# projet_electronique.net
KiCad netlist of a schematic drawn in EAGLE
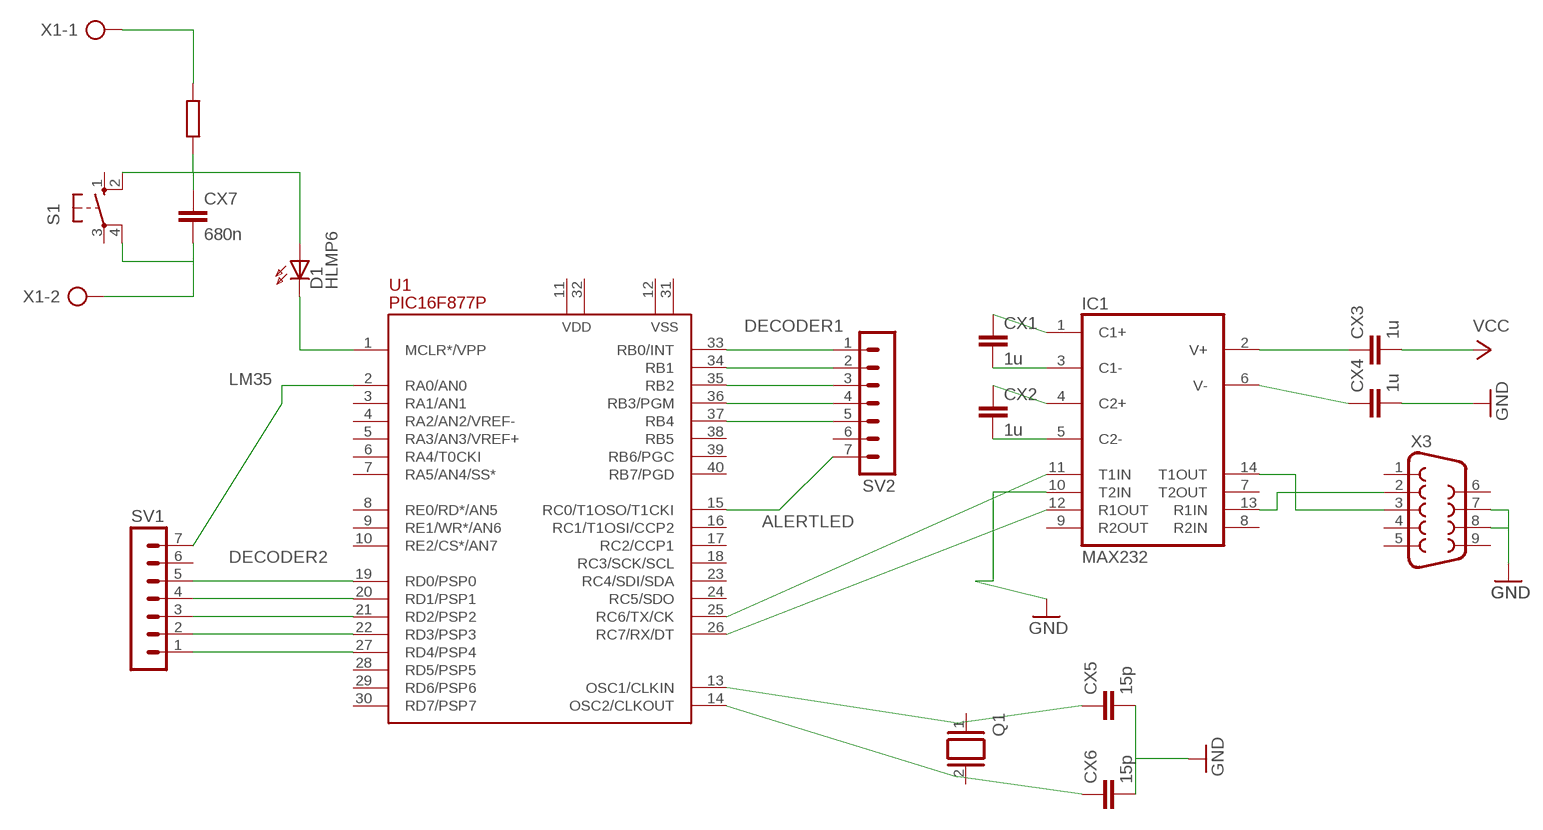
[diagram p0: schematic, sheet 1]

(export (version "E")
  (design (tool "Eeschema 10.0.6"))
  (components
    (comp (ref "CX1")
      (value "1u")
      (footprint "eagle-import:XC10B5")
      (libsource (lib "eagle-import") (part "CXXC10B5"))
    )
    (comp (ref "CX2")
      (value "1u")
      (footprint "eagle-import:XC10B5")
      (libsource (lib "eagle-import") (part "CXXC10B5"))
    )
    (comp (ref "CX3")
      (value "1u")
      (footprint "eagle-import:XC10B5")
      (libsource (lib "eagle-import") (part "CXXC10B5"))
    )
    (comp (ref "CX4")
      (value "1u")
      (footprint "eagle-import:XC10B5")
      (libsource (lib "eagle-import") (part "CXXC10B5"))
    )
    (comp (ref "CX5")
      (value "15p")
      (footprint "eagle-import:XC10B5")
      (libsource (lib "eagle-import") (part "CXXC10B5"))
    )
    (comp (ref "CX6")
      (value "15p")
      (footprint "eagle-import:XC10B5")
      (libsource (lib "eagle-import") (part "CXXC10B5"))
    )
    (comp (ref "CX7")
      (value "680n")
      (footprint "eagle-import:XC10B5")
      (libsource (lib "eagle-import") (part "CXXC10B5"))
    )
    (comp (ref "D1")
      (value "HLMP6")
      (footprint "eagle-import:HLMP6")
      (fields (field (name "MF") "AGILENT TECHNOLOGIES") (field (name "MPN") "HLMP-6500"))
      (libsource (lib "eagle-import") (part "HLMP6"))
    )
    (comp (ref "IC1")
      (value "MAX232")
      (footprint "eagle-import:DIL16")
      (fields (field (name "MF") "MAXIM") (field (name "MPN") "MAX232ACPE+"))
      (libsource (lib "eagle-import") (part "MAX232"))
    )
    (comp (ref "Q1")
      (value "XTAL")
      (footprint "eagle-import:Q")
      (libsource (lib "eagle-import") (part "XTAL"))
    )
    (comp (ref "S1")
      (value "10-XX")
      (footprint "eagle-import:B3F-10XX")
      (fields (field (name "MPN") "B3F-1000"))
      (libsource (lib "eagle-import") (part "10-XX"))
    )
    (comp (ref "SV1")
      (value "MA07-1")
      (footprint "eagle-import:MA07-1")
      (libsource (lib "eagle-import") (part "MA07-1"))
    )
    (comp (ref "SV2")
      (value "MA07-1")
      (footprint "eagle-import:MA07-1")
      (libsource (lib "eagle-import") (part "MA07-1"))
    )
    (comp (ref "U1")
      (value "PIC16F877P")
      (footprint "eagle-import:DIL40")
      (libsource (lib "eagle-import") (part "PIC16F877P"))
    )
    (comp (ref "X1")
      (value "AK500/2-H")
      (footprint "eagle-import:AK500_2-H")
      (libsource (lib "eagle-import") (part "AK500/2-H"))
    )
    (comp (ref "X3")
      (value "F09V")
      (footprint "eagle-import:F09V")
      (libsource (lib "eagle-import") (part "F09V"))
    )
  )
  (nets
    (net (code "1") (name "/ALERTLED") (class "Default")
      (node (ref "SV2") (pin "7") (pinfunction "7_7") (pintype "passive"))
      (node (ref "U1") (pin "15") (pinfunction "RC0/T1OSO/T1CKI_15") (pintype "bidirectional"))
    )
    (net (code "2") (name "/DECODER1") (class "Default")
      (node (ref "SV2") (pin "1") (pinfunction "1_1") (pintype "passive"))
      (node (ref "U1") (pin "33") (pinfunction "RB0/INT_33") (pintype "bidirectional"))
    )
    (net (code "3") (name "/DECODER2") (class "Default")
      (node (ref "SV1") (pin "5") (pinfunction "5_5") (pintype "passive"))
      (node (ref "U1") (pin "19") (pinfunction "RD0/PSP0_19") (pintype "bidirectional"))
    )
    (net (code "4") (name "/LM35") (class "Default")
      (node (ref "SV1") (pin "7") (pinfunction "7_7") (pintype "passive"))
      (node (ref "U1") (pin "2") (pinfunction "RA0/AN0_2") (pintype "bidirectional"))
    )
    (net (code "5") (name "GND") (class "Default")
      (node (ref "CX4") (pin "2") (pinfunction "2_2") (pintype "passive"))
      (node (ref "CX5") (pin "2") (pinfunction "2_2") (pintype "passive"))
      (node (ref "CX6") (pin "2") (pinfunction "2_2") (pintype "passive"))
      (node (ref "IC1") (pin "10") (pinfunction "T2IN_10") (pintype "input"))
      (node (ref "X3") (pin "7") (pinfunction "7_7") (pintype "passive"))
      (node (ref "X3") (pin "8") (pinfunction "8_8") (pintype "passive"))
    )
    (net (code "6") (name "Net-(IC1A-C1+)") (class "Default")
      (node (ref "CX1") (pin "1") (pinfunction "1_1") (pintype "passive"))
      (node (ref "IC1") (pin "1") (pinfunction "C1+_1") (pintype "bidirectional"))
    )
    (net (code "7") (name "Net-(IC1A-C1-)") (class "Default")
      (node (ref "CX1") (pin "2") (pinfunction "2_2") (pintype "passive"))
      (node (ref "IC1") (pin "3") (pinfunction "C1-_3") (pintype "bidirectional"))
    )
    (net (code "8") (name "Net-(IC1A-C2+)") (class "Default")
      (node (ref "CX2") (pin "1") (pinfunction "1_1") (pintype "passive"))
      (node (ref "IC1") (pin "4") (pinfunction "C2+_4") (pintype "bidirectional"))
    )
    (net (code "9") (name "Net-(IC1A-C2-)") (class "Default")
      (node (ref "CX2") (pin "2") (pinfunction "2_2") (pintype "passive"))
      (node (ref "IC1") (pin "5") (pinfunction "C2-_5") (pintype "bidirectional"))
    )
    (net (code "10") (name "Net-(IC1A-R1IN)") (class "Default")
      (node (ref "IC1") (pin "13") (pinfunction "R1IN_13") (pintype "input"))
      (node (ref "X3") (pin "2") (pinfunction "2_2") (pintype "passive"))
    )
    (net (code "11") (name "Net-(IC1A-R1OUT)") (class "Default")
      (node (ref "IC1") (pin "12") (pinfunction "R1OUT_12") (pintype "output"))
      (node (ref "U1") (pin "26") (pinfunction "RC7/RX/DT_26") (pintype "bidirectional"))
    )
    (net (code "12") (name "Net-(IC1A-T1IN)") (class "Default")
      (node (ref "IC1") (pin "11") (pinfunction "T1IN_11") (pintype "input"))
      (node (ref "U1") (pin "25") (pinfunction "RC6/TX/CK_25") (pintype "bidirectional"))
    )
    (net (code "13") (name "Net-(IC1A-T1OUT)") (class "Default")
      (node (ref "IC1") (pin "14") (pinfunction "T1OUT_14") (pintype "output"))
      (node (ref "X3") (pin "3") (pinfunction "3_3") (pintype "passive"))
    )
    (net (code "14") (name "Net-(IC1A-V+)") (class "Default")
      (node (ref "CX3") (pin "1") (pinfunction "1_1") (pintype "passive"))
      (node (ref "IC1") (pin "2") (pinfunction "V+_2") (pintype "bidirectional"))
    )
    (net (code "15") (name "Net-(IC1A-V-)") (class "Default")
      (node (ref "CX4") (pin "1") (pinfunction "1_1") (pintype "passive"))
      (node (ref "IC1") (pin "6") (pinfunction "V-_6") (pintype "bidirectional"))
    )
    (net (code "16") (name "Net-(S1-P1)") (class "Default")
      (node (ref "CX7") (pin "2") (pinfunction "2_2") (pintype "passive"))
      (node (ref "S1") (pin "4") (pinfunction "P1_4") (pintype "passive"))
      (node (ref "X1") (pin "2") (pinfunction "KL_2") (pintype "passive"))
    )
    (net (code "17") (name "Net-(S1-S1)") (class "Default")
      (node (ref "CX7") (pin "1") (pinfunction "1_1") (pintype "passive"))
      (node (ref "D1") (pin "A") (pinfunction "A_A") (pintype "passive"))
      (node (ref "S1") (pin "2") (pinfunction "S1_2") (pintype "passive"))
    )
    (net (code "18") (name "Net-(U1-MCLR*{slash}VPP)") (class "Default")
      (node (ref "D1") (pin "K") (pinfunction "K_K") (pintype "passive"))
      (node (ref "U1") (pin "1") (pinfunction "MCLR*/VPP_1") (pintype "input"))
    )
    (net (code "19") (name "Net-(U1-OSC1{slash}CLKIN)") (class "Default")
      (node (ref "CX5") (pin "1") (pinfunction "1_1") (pintype "passive"))
      (node (ref "U1") (pin "13") (pinfunction "OSC1/CLKIN_13") (pintype "input"))
    )
    (net (code "20") (name "Net-(U1-OSC2{slash}CLKOUT)") (class "Default")
      (node (ref "CX6") (pin "1") (pinfunction "1_1") (pintype "passive"))
      (node (ref "U1") (pin "14") (pinfunction "OSC2/CLKOUT_14") (pintype "output"))
    )
    (net (code "21") (name "Net-(U1-RB1)") (class "Default")
      (node (ref "SV2") (pin "2") (pinfunction "2_2") (pintype "passive"))
      (node (ref "U1") (pin "34") (pinfunction "RB1_34") (pintype "bidirectional"))
    )
    (net (code "22") (name "Net-(U1-RB2)") (class "Default")
      (node (ref "SV2") (pin "3") (pinfunction "3_3") (pintype "passive"))
      (node (ref "U1") (pin "35") (pinfunction "RB2_35") (pintype "bidirectional"))
    )
    (net (code "23") (name "Net-(U1-RB3{slash}PGM)") (class "Default")
      (node (ref "SV2") (pin "4") (pinfunction "4_4") (pintype "passive"))
      (node (ref "U1") (pin "36") (pinfunction "RB3/PGM_36") (pintype "bidirectional"))
    )
    (net (code "24") (name "Net-(U1-RB4)") (class "Default")
      (node (ref "SV2") (pin "5") (pinfunction "5_5") (pintype "passive"))
      (node (ref "U1") (pin "37") (pinfunction "RB4_37") (pintype "bidirectional"))
    )
    (net (code "25") (name "Net-(U1-RD1{slash}PSP1)") (class "Default")
      (node (ref "SV1") (pin "4") (pinfunction "4_4") (pintype "passive"))
      (node (ref "U1") (pin "20") (pinfunction "RD1/PSP1_20") (pintype "bidirectional"))
    )
    (net (code "26") (name "Net-(U1-RD2{slash}PSP2)") (class "Default")
      (node (ref "SV1") (pin "3") (pinfunction "3_3") (pintype "passive"))
      (node (ref "U1") (pin "21") (pinfunction "RD2/PSP2_21") (pintype "bidirectional"))
    )
    (net (code "27") (name "Net-(U1-RD3{slash}PSP3)") (class "Default")
      (node (ref "SV1") (pin "2") (pinfunction "2_2") (pintype "passive"))
      (node (ref "U1") (pin "22") (pinfunction "RD3/PSP3_22") (pintype "bidirectional"))
    )
    (net (code "28") (name "Net-(U1-RD4{slash}PSP4)") (class "Default")
      (node (ref "SV1") (pin "1") (pinfunction "1_1") (pintype "passive"))
      (node (ref "U1") (pin "27") (pinfunction "RD4/PSP4_27") (pintype "bidirectional"))
    )
    (net (code "29") (name "VCC") (class "Default")
      (node (ref "CX3") (pin "2") (pinfunction "2_2") (pintype "passive"))
    )
    (net (code "30") (name "unconnected-(IC1A-R2IN-Pad8)") (class "Default")
      (node (ref "IC1") (pin "8") (pinfunction "R2IN_8") (pintype "input"))
    )
    (net (code "31") (name "unconnected-(IC1A-R2OUT-Pad9)") (class "Default")
      (node (ref "IC1") (pin "9") (pinfunction "R2OUT_9") (pintype "output"))
    )
    (net (code "32") (name "unconnected-(IC1A-T2OUT-Pad7)") (class "Default")
      (node (ref "IC1") (pin "7") (pinfunction "T2OUT_7") (pintype "output"))
    )
    (net (code "33") (name "unconnected-(Q1-Pad1)") (class "Default")
      (node (ref "Q1") (pin "1") (pinfunction "1_1") (pintype "passive"))
    )
    (net (code "34") (name "unconnected-(Q1-Pad2)") (class "Default")
      (node (ref "Q1") (pin "2") (pinfunction "2_2") (pintype "passive"))
    )
    (net (code "35") (name "unconnected-(S1-P-Pad3)") (class "Default")
      (node (ref "S1") (pin "3") (pinfunction "P_3") (pintype "passive"))
    )
    (net (code "36") (name "unconnected-(S1-S-Pad1)") (class "Default")
      (node (ref "S1") (pin "1") (pinfunction "S_1") (pintype "passive"))
    )
    (net (code "37") (name "unconnected-(SV1-Pad6)") (class "Default")
      (node (ref "SV1") (pin "6") (pinfunction "6_6") (pintype "passive"))
    )
    (net (code "38") (name "unconnected-(SV2-Pad6)") (class "Default")
      (node (ref "SV2") (pin "6") (pinfunction "6_6") (pintype "passive"))
    )
    (net (code "39") (name "unconnected-(U1-RA1{slash}AN1-Pad3)") (class "Default")
      (node (ref "U1") (pin "3") (pinfunction "RA1/AN1_3") (pintype "bidirectional"))
    )
    (net (code "40") (name "unconnected-(U1-RA2{slash}AN2{slash}VREF--Pad4)") (class "Default")
      (node (ref "U1") (pin "4") (pinfunction "RA2/AN2/VREF-_4") (pintype "bidirectional"))
    )
    (net (code "41") (name "unconnected-(U1-RA3{slash}AN3{slash}VREF+-Pad5)") (class "Default")
      (node (ref "U1") (pin "5") (pinfunction "RA3/AN3/VREF+_5") (pintype "bidirectional"))
    )
    (net (code "42") (name "unconnected-(U1-RA4{slash}T0CKI-Pad6)") (class "Default")
      (node (ref "U1") (pin "6") (pinfunction "RA4/T0CKI_6") (pintype "bidirectional"))
    )
    (net (code "43") (name "unconnected-(U1-RA5{slash}AN4{slash}SS*-Pad7)") (class "Default")
      (node (ref "U1") (pin "7") (pinfunction "RA5/AN4/SS*_7") (pintype "bidirectional"))
    )
    (net (code "44") (name "unconnected-(U1-RB5-Pad38)") (class "Default")
      (node (ref "U1") (pin "38") (pinfunction "RB5_38") (pintype "bidirectional"))
    )
    (net (code "45") (name "unconnected-(U1-RB6{slash}PGC-Pad39)") (class "Default")
      (node (ref "U1") (pin "39") (pinfunction "RB6/PGC_39") (pintype "bidirectional"))
    )
    (net (code "46") (name "unconnected-(U1-RB7{slash}PGD-Pad40)") (class "Default")
      (node (ref "U1") (pin "40") (pinfunction "RB7/PGD_40") (pintype "bidirectional"))
    )
    (net (code "47") (name "unconnected-(U1-RC1{slash}T1OSI{slash}CCP2-Pad16)") (class "Default")
      (node (ref "U1") (pin "16") (pinfunction "RC1/T1OSI/CCP2_16") (pintype "bidirectional"))
    )
    (net (code "48") (name "unconnected-(U1-RC2{slash}CCP1-Pad17)") (class "Default")
      (node (ref "U1") (pin "17") (pinfunction "RC2/CCP1_17") (pintype "bidirectional"))
    )
    (net (code "49") (name "unconnected-(U1-RC3{slash}SCK{slash}SCL-Pad18)") (class "Default")
      (node (ref "U1") (pin "18") (pinfunction "RC3/SCK/SCL_18") (pintype "bidirectional"))
    )
    (net (code "50") (name "unconnected-(U1-RC4{slash}SDI{slash}SDA-Pad23)") (class "Default")
      (node (ref "U1") (pin "23") (pinfunction "RC4/SDI/SDA_23") (pintype "bidirectional"))
    )
    (net (code "51") (name "unconnected-(U1-RC5{slash}SDO-Pad24)") (class "Default")
      (node (ref "U1") (pin "24") (pinfunction "RC5/SDO_24") (pintype "bidirectional"))
    )
    (net (code "52") (name "unconnected-(U1-RD5{slash}PSP5-Pad28)") (class "Default")
      (node (ref "U1") (pin "28") (pinfunction "RD5/PSP5_28") (pintype "bidirectional"))
    )
    (net (code "53") (name "unconnected-(U1-RD6{slash}PSP6-Pad29)") (class "Default")
      (node (ref "U1") (pin "29") (pinfunction "RD6/PSP6_29") (pintype "bidirectional"))
    )
    (net (code "54") (name "unconnected-(U1-RD7{slash}PSP7-Pad30)") (class "Default")
      (node (ref "U1") (pin "30") (pinfunction "RD7/PSP7_30") (pintype "bidirectional"))
    )
    (net (code "55") (name "unconnected-(U1-RE0{slash}RD*{slash}AN5-Pad8)") (class "Default")
      (node (ref "U1") (pin "8") (pinfunction "RE0/RD*/AN5_8") (pintype "bidirectional"))
    )
    (net (code "56") (name "unconnected-(U1-RE1{slash}WR*{slash}AN6-Pad9)") (class "Default")
      (node (ref "U1") (pin "9") (pinfunction "RE1/WR*/AN6_9") (pintype "bidirectional"))
    )
    (net (code "57") (name "unconnected-(U1-RE2{slash}CS*{slash}AN7-Pad10)") (class "Default")
      (node (ref "U1") (pin "10") (pinfunction "RE2/CS*/AN7_10") (pintype "bidirectional"))
    )
    (net (code "58") (name "unconnected-(U1-VDD-Pad11)") (class "Default")
      (node (ref "U1") (pin "11") (pinfunction "VDD_11") (pintype "bidirectional"))
    )
    (net (code "59") (name "unconnected-(U1-VDD-Pad32)") (class "Default")
      (node (ref "U1") (pin "32") (pinfunction "VDD_32") (pintype "bidirectional"))
    )
    (net (code "60") (name "unconnected-(U1-VSS-Pad12)") (class "Default")
      (node (ref "U1") (pin "12") (pinfunction "VSS_12") (pintype "bidirectional"))
    )
    (net (code "61") (name "unconnected-(U1-VSS-Pad31)") (class "Default")
      (node (ref "U1") (pin "31") (pinfunction "VSS_31") (pintype "bidirectional"))
    )
    (net (code "62") (name "unconnected-(X1A-KL-Pad1)") (class "Default")
      (node (ref "X1") (pin "1") (pinfunction "KL_1") (pintype "passive"))
    )
    (net (code "63") (name "unconnected-(X3-Pad1)") (class "Default")
      (node (ref "X3") (pin "1") (pinfunction "1_1") (pintype "passive"))
    )
    (net (code "64") (name "unconnected-(X3-Pad4)") (class "Default")
      (node (ref "X3") (pin "4") (pinfunction "4_4") (pintype "passive"))
    )
    (net (code "65") (name "unconnected-(X3-Pad5)") (class "Default")
      (node (ref "X3") (pin "5") (pinfunction "5_5") (pintype "passive"))
    )
    (net (code "66") (name "unconnected-(X3-Pad6)") (class "Default")
      (node (ref "X3") (pin "6") (pinfunction "6_6") (pintype "passive"))
    )
    (net (code "67") (name "unconnected-(X3-Pad9)") (class "Default")
      (node (ref "X3") (pin "9") (pinfunction "9_9") (pintype "passive"))
    )
  )
)
